# M632B.net
KiCad netlist of a schematic drawn in EAGLE
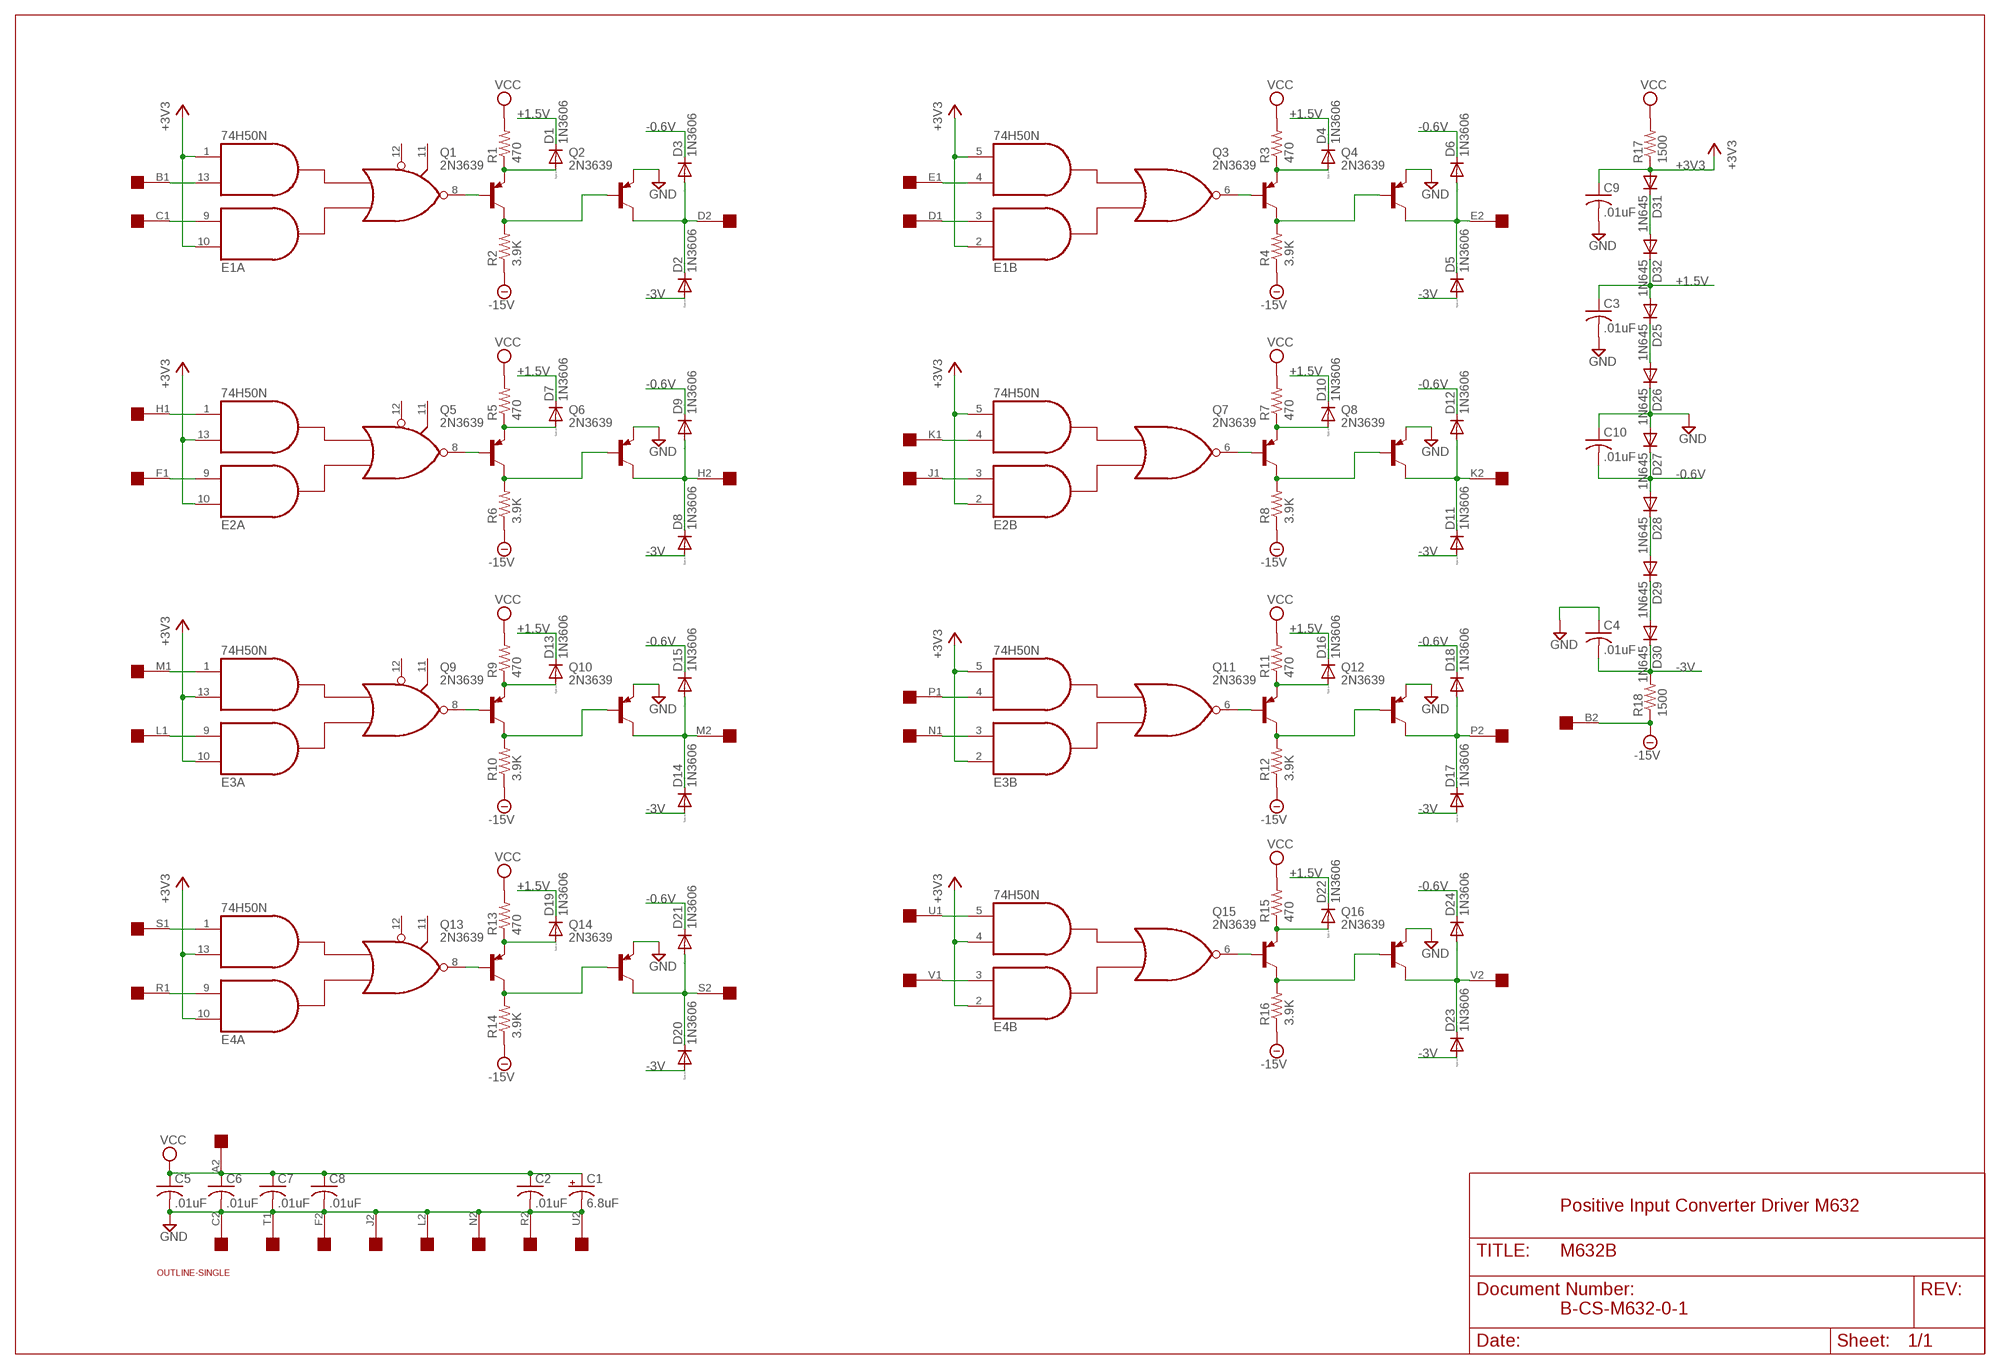
[diagram p0: schematic, sheet 1]

(export (version "E")
  (design (tool "Eeschema 10.0.6"))
  (components
    (comp (ref "C1")
      (value "6.8uF")
      (footprint "eagle-import:E12-8")
      (libsource (lib "eagle-import") (part "CPOL-USE20-8AXIAL"))
    )
    (comp (ref "C2")
      (value ".01uF")
      (footprint "eagle-import:C050-025X075")
      (libsource (lib "eagle-import") (part "C-US050-025X075"))
    )
    (comp (ref "C3")
      (value ".01uF")
      (footprint "eagle-import:C050-025X075")
      (libsource (lib "eagle-import") (part "C-US050-025X075"))
    )
    (comp (ref "C4")
      (value ".01uF")
      (footprint "eagle-import:C050-025X075")
      (libsource (lib "eagle-import") (part "C-US050-025X075"))
    )
    (comp (ref "C5")
      (value ".01uF")
      (footprint "eagle-import:C050-025X075")
      (libsource (lib "eagle-import") (part "C-US050-025X075"))
    )
    (comp (ref "C6")
      (value ".01uF")
      (footprint "eagle-import:C050-025X075")
      (libsource (lib "eagle-import") (part "C-US050-025X075"))
    )
    (comp (ref "C7")
      (value ".01uF")
      (footprint "eagle-import:C050-025X075")
      (libsource (lib "eagle-import") (part "C-US050-025X075"))
    )
    (comp (ref "C8")
      (value ".01uF")
      (footprint "eagle-import:C050-025X075")
      (libsource (lib "eagle-import") (part "C-US050-025X075"))
    )
    (comp (ref "C9")
      (value ".01uF")
      (footprint "eagle-import:C050-025X075")
      (libsource (lib "eagle-import") (part "C-US050-025X075"))
    )
    (comp (ref "C10")
      (value ".01uF")
      (footprint "eagle-import:C050-025X075")
      (libsource (lib "eagle-import") (part "C-US050-025X075"))
    )
    (comp (ref "D1")
      (value "1N3606")
      (footprint "eagle-import:DO35-10")
      (libsource (lib "eagle-import") (part "1N4148DO35-10"))
    )
    (comp (ref "D2")
      (value "1N3606")
      (footprint "eagle-import:DO35-10")
      (libsource (lib "eagle-import") (part "1N4148DO35-10"))
    )
    (comp (ref "D3")
      (value "1N3606")
      (footprint "eagle-import:DO35-10")
      (libsource (lib "eagle-import") (part "1N4148DO35-10"))
    )
    (comp (ref "D4")
      (value "1N3606")
      (footprint "eagle-import:DO35-10")
      (libsource (lib "eagle-import") (part "1N4148DO35-10"))
    )
    (comp (ref "D5")
      (value "1N3606")
      (footprint "eagle-import:DO35-10")
      (libsource (lib "eagle-import") (part "1N4148DO35-10"))
    )
    (comp (ref "D6")
      (value "1N3606")
      (footprint "eagle-import:DO35-10")
      (libsource (lib "eagle-import") (part "1N4148DO35-10"))
    )
    (comp (ref "D7")
      (value "1N3606")
      (footprint "eagle-import:DO35-10")
      (libsource (lib "eagle-import") (part "1N4148DO35-10"))
    )
    (comp (ref "D8")
      (value "1N3606")
      (footprint "eagle-import:DO35-10")
      (libsource (lib "eagle-import") (part "1N4148DO35-10"))
    )
    (comp (ref "D9")
      (value "1N3606")
      (footprint "eagle-import:DO35-10")
      (libsource (lib "eagle-import") (part "1N4148DO35-10"))
    )
    (comp (ref "D10")
      (value "1N3606")
      (footprint "eagle-import:DO35-10")
      (libsource (lib "eagle-import") (part "1N4148DO35-10"))
    )
    (comp (ref "D11")
      (value "1N3606")
      (footprint "eagle-import:DO35-10")
      (libsource (lib "eagle-import") (part "1N4148DO35-10"))
    )
    (comp (ref "D12")
      (value "1N3606")
      (footprint "eagle-import:DO35-10")
      (libsource (lib "eagle-import") (part "1N4148DO35-10"))
    )
    (comp (ref "D13")
      (value "1N3606")
      (footprint "eagle-import:DO35-10")
      (libsource (lib "eagle-import") (part "1N4148DO35-10"))
    )
    (comp (ref "D14")
      (value "1N3606")
      (footprint "eagle-import:DO35-10")
      (libsource (lib "eagle-import") (part "1N4148DO35-10"))
    )
    (comp (ref "D15")
      (value "1N3606")
      (footprint "eagle-import:DO35-10")
      (libsource (lib "eagle-import") (part "1N4148DO35-10"))
    )
    (comp (ref "D16")
      (value "1N3606")
      (footprint "eagle-import:DO35-10")
      (libsource (lib "eagle-import") (part "1N4148DO35-10"))
    )
    (comp (ref "D17")
      (value "1N3606")
      (footprint "eagle-import:DO35-10")
      (libsource (lib "eagle-import") (part "1N4148DO35-10"))
    )
    (comp (ref "D18")
      (value "1N3606")
      (footprint "eagle-import:DO35-10")
      (libsource (lib "eagle-import") (part "1N4148DO35-10"))
    )
    (comp (ref "D19")
      (value "1N3606")
      (footprint "eagle-import:DO35-10")
      (libsource (lib "eagle-import") (part "1N4148DO35-10"))
    )
    (comp (ref "D20")
      (value "1N3606")
      (footprint "eagle-import:DO35-10")
      (libsource (lib "eagle-import") (part "1N4148DO35-10"))
    )
    (comp (ref "D21")
      (value "1N3606")
      (footprint "eagle-import:DO35-10")
      (libsource (lib "eagle-import") (part "1N4148DO35-10"))
    )
    (comp (ref "D22")
      (value "1N3606")
      (footprint "eagle-import:DO35-10")
      (libsource (lib "eagle-import") (part "1N4148DO35-10"))
    )
    (comp (ref "D23")
      (value "1N3606")
      (footprint "eagle-import:DO35-10")
      (libsource (lib "eagle-import") (part "1N4148DO35-10"))
    )
    (comp (ref "D24")
      (value "1N3606")
      (footprint "eagle-import:DO35-10")
      (libsource (lib "eagle-import") (part "1N4148DO35-10"))
    )
    (comp (ref "D25")
      (value "1N645")
      (footprint "eagle-import:DO35-10")
      (libsource (lib "eagle-import") (part "1N4148DO35-10"))
    )
    (comp (ref "D26")
      (value "1N645")
      (footprint "eagle-import:DO35-10")
      (libsource (lib "eagle-import") (part "1N4148DO35-10"))
    )
    (comp (ref "D27")
      (value "1N645")
      (footprint "eagle-import:DO35-10")
      (libsource (lib "eagle-import") (part "1N4148DO35-10"))
    )
    (comp (ref "D28")
      (value "1N645")
      (footprint "eagle-import:DO35-10")
      (libsource (lib "eagle-import") (part "1N4148DO35-10"))
    )
    (comp (ref "D29")
      (value "1N645")
      (footprint "eagle-import:DO35-10")
      (libsource (lib "eagle-import") (part "1N4148DO35-10"))
    )
    (comp (ref "D30")
      (value "1N645")
      (footprint "eagle-import:DO35-10")
      (libsource (lib "eagle-import") (part "1N4148DO35-10"))
    )
    (comp (ref "D31")
      (value "1N645")
      (footprint "eagle-import:DO35-10")
      (libsource (lib "eagle-import") (part "1N4148DO35-10"))
    )
    (comp (ref "D32")
      (value "1N645")
      (footprint "eagle-import:DO35-10")
      (libsource (lib "eagle-import") (part "1N4148DO35-10"))
    )
    (comp (ref "E1")
      (value "74H50N")
      (footprint "eagle-import:DIL14")
      (libsource (lib "eagle-import") (part "7450N"))
    )
    (comp (ref "E2")
      (value "74H50N")
      (footprint "eagle-import:DIL14")
      (libsource (lib "eagle-import") (part "7450N"))
    )
    (comp (ref "E3")
      (value "74H50N")
      (footprint "eagle-import:DIL14")
      (libsource (lib "eagle-import") (part "7450N"))
    )
    (comp (ref "E4")
      (value "74H50N")
      (footprint "eagle-import:DIL14")
      (libsource (lib "eagle-import") (part "7450N"))
    )
    (comp (ref "Q1")
      (value "2N3639")
      (footprint "eagle-import:TO39")
      (libsource (lib "eagle-import") (part "2N2904"))
    )
    (comp (ref "Q2")
      (value "2N3639")
      (footprint "eagle-import:TO39")
      (libsource (lib "eagle-import") (part "2N2904"))
    )
    (comp (ref "Q3")
      (value "2N3639")
      (footprint "eagle-import:TO39")
      (libsource (lib "eagle-import") (part "2N2904"))
    )
    (comp (ref "Q4")
      (value "2N3639")
      (footprint "eagle-import:TO39")
      (libsource (lib "eagle-import") (part "2N2904"))
    )
    (comp (ref "Q5")
      (value "2N3639")
      (footprint "eagle-import:TO39")
      (libsource (lib "eagle-import") (part "2N2904"))
    )
    (comp (ref "Q6")
      (value "2N3639")
      (footprint "eagle-import:TO39")
      (libsource (lib "eagle-import") (part "2N2904"))
    )
    (comp (ref "Q7")
      (value "2N3639")
      (footprint "eagle-import:TO39")
      (libsource (lib "eagle-import") (part "2N2904"))
    )
    (comp (ref "Q8")
      (value "2N3639")
      (footprint "eagle-import:TO39")
      (libsource (lib "eagle-import") (part "2N2904"))
    )
    (comp (ref "Q9")
      (value "2N3639")
      (footprint "eagle-import:TO39")
      (libsource (lib "eagle-import") (part "2N2904"))
    )
    (comp (ref "Q10")
      (value "2N3639")
      (footprint "eagle-import:TO39")
      (libsource (lib "eagle-import") (part "2N2904"))
    )
    (comp (ref "Q11")
      (value "2N3639")
      (footprint "eagle-import:TO39")
      (libsource (lib "eagle-import") (part "2N2904"))
    )
    (comp (ref "Q12")
      (value "2N3639")
      (footprint "eagle-import:TO39")
      (libsource (lib "eagle-import") (part "2N2904"))
    )
    (comp (ref "Q13")
      (value "2N3639")
      (footprint "eagle-import:TO39")
      (libsource (lib "eagle-import") (part "2N2904"))
    )
    (comp (ref "Q14")
      (value "2N3639")
      (footprint "eagle-import:TO39")
      (libsource (lib "eagle-import") (part "2N2904"))
    )
    (comp (ref "Q15")
      (value "2N3639")
      (footprint "eagle-import:TO39")
      (libsource (lib "eagle-import") (part "2N2904"))
    )
    (comp (ref "Q16")
      (value "2N3639")
      (footprint "eagle-import:TO39")
      (libsource (lib "eagle-import") (part "2N2904"))
    )
    (comp (ref "R1")
      (value "470")
      (footprint "eagle-import:0207_10")
      (libsource (lib "eagle-import") (part "R-US_0207/10"))
    )
    (comp (ref "R2")
      (value "3.9K")
      (footprint "eagle-import:0207_10")
      (libsource (lib "eagle-import") (part "R-US_0207/10"))
    )
    (comp (ref "R3")
      (value "470")
      (footprint "eagle-import:0207_10")
      (libsource (lib "eagle-import") (part "R-US_0207/10"))
    )
    (comp (ref "R4")
      (value "3.9K")
      (footprint "eagle-import:0207_10")
      (libsource (lib "eagle-import") (part "R-US_0207/10"))
    )
    (comp (ref "R5")
      (value "470")
      (footprint "eagle-import:0207_10")
      (libsource (lib "eagle-import") (part "R-US_0207/10"))
    )
    (comp (ref "R6")
      (value "3.9K")
      (footprint "eagle-import:0207_10")
      (libsource (lib "eagle-import") (part "R-US_0207/10"))
    )
    (comp (ref "R7")
      (value "470")
      (footprint "eagle-import:0207_10")
      (libsource (lib "eagle-import") (part "R-US_0207/10"))
    )
    (comp (ref "R8")
      (value "3.9K")
      (footprint "eagle-import:0207_10")
      (libsource (lib "eagle-import") (part "R-US_0207/10"))
    )
    (comp (ref "R9")
      (value "470")
      (footprint "eagle-import:0207_10")
      (libsource (lib "eagle-import") (part "R-US_0207/10"))
    )
    (comp (ref "R10")
      (value "3.9K")
      (footprint "eagle-import:0207_10")
      (libsource (lib "eagle-import") (part "R-US_0207/10"))
    )
    (comp (ref "R11")
      (value "470")
      (footprint "eagle-import:0207_10")
      (libsource (lib "eagle-import") (part "R-US_0207/10"))
    )
    (comp (ref "R12")
      (value "3.9K")
      (footprint "eagle-import:0207_10")
      (libsource (lib "eagle-import") (part "R-US_0207/10"))
    )
    (comp (ref "R13")
      (value "470")
      (footprint "eagle-import:0207_10")
      (libsource (lib "eagle-import") (part "R-US_0207/10"))
    )
    (comp (ref "R14")
      (value "3.9K")
      (footprint "eagle-import:0207_10")
      (libsource (lib "eagle-import") (part "R-US_0207/10"))
    )
    (comp (ref "R15")
      (value "470")
      (footprint "eagle-import:0207_10")
      (libsource (lib "eagle-import") (part "R-US_0207/10"))
    )
    (comp (ref "R16")
      (value "3.9K")
      (footprint "eagle-import:0207_10")
      (libsource (lib "eagle-import") (part "R-US_0207/10"))
    )
    (comp (ref "R17")
      (value "1500")
      (footprint "eagle-import:0207_10")
      (libsource (lib "eagle-import") (part "R-US_0207/10"))
    )
    (comp (ref "R18")
      (value "1500")
      (footprint "eagle-import:0207_10")
      (libsource (lib "eagle-import") (part "R-US_0207/10"))
    )
    (comp (ref "U$1")
      (value "SINGLE")
      (footprint "eagle-import:EDGE-CON2")
      (libsource (lib "eagle-import") (part "SINGLE"))
    )
    (comp (ref "U$4")
      (value "OUTLINE-SINGLE")
      (footprint "eagle-import:SINGLE")
      (libsource (lib "eagle-import") (part "OUTLINE-SINGLE"))
    )
  )
  (nets
    (net (code "1") (name "+3V3") (class "Default")
      (node (ref "C9") (pin "1") (pinfunction "1_1") (pintype "passive"))
      (node (ref "D31") (pin "A") (pinfunction "A_A") (pintype "passive"))
      (node (ref "E1") (pin "1") (pinfunction "I4_1") (pintype "input"))
      (node (ref "E1") (pin "10") (pinfunction "I1_10") (pintype "input"))
      (node (ref "E1") (pin "2") (pinfunction "I1_2") (pintype "input"))
      (node (ref "E1") (pin "5") (pinfunction "I4_5") (pintype "input"))
      (node (ref "E2") (pin "10") (pinfunction "I1_10") (pintype "input"))
      (node (ref "E2") (pin "13") (pinfunction "I3_13") (pintype "input"))
      (node (ref "E2") (pin "2") (pinfunction "I1_2") (pintype "input"))
      (node (ref "E2") (pin "5") (pinfunction "I4_5") (pintype "input"))
      (node (ref "E3") (pin "10") (pinfunction "I1_10") (pintype "input"))
      (node (ref "E3") (pin "13") (pinfunction "I3_13") (pintype "input"))
      (node (ref "E3") (pin "2") (pinfunction "I1_2") (pintype "input"))
      (node (ref "E3") (pin "5") (pinfunction "I4_5") (pintype "input"))
      (node (ref "E4") (pin "10") (pinfunction "I1_10") (pintype "input"))
      (node (ref "E4") (pin "13") (pinfunction "I3_13") (pintype "input"))
      (node (ref "E4") (pin "2") (pinfunction "I1_2") (pintype "input"))
      (node (ref "E4") (pin "4") (pinfunction "I3_4") (pintype "input"))
      (node (ref "R17") (pin "1") (pinfunction "1_1") (pintype "passive"))
    )
    (net (code "2") (name "-15V") (class "Default")
      (node (ref "R10") (pin "1") (pinfunction "1_1") (pintype "passive"))
      (node (ref "R12") (pin "1") (pinfunction "1_1") (pintype "passive"))
      (node (ref "R14") (pin "1") (pinfunction "1_1") (pintype "passive"))
      (node (ref "R16") (pin "1") (pinfunction "1_1") (pintype "passive"))
      (node (ref "R18") (pin "1") (pinfunction "1_1") (pintype "passive"))
      (node (ref "R2") (pin "1") (pinfunction "1_1") (pintype "passive"))
      (node (ref "R4") (pin "1") (pinfunction "1_1") (pintype "passive"))
      (node (ref "R6") (pin "1") (pinfunction "1_1") (pintype "passive"))
      (node (ref "R8") (pin "1") (pinfunction "1_1") (pintype "passive"))
      (node (ref "U$1") (pin "B2") (pinfunction "1_B2") (pintype "bidirectional"))
    )
    (net (code "3") (name "/+1.5V") (class "Default")
      (node (ref "C3") (pin "1") (pinfunction "1_1") (pintype "passive"))
      (node (ref "D1") (pin "C") (pinfunction "C_C") (pintype "passive"))
      (node (ref "D10") (pin "C") (pinfunction "C_C") (pintype "passive"))
      (node (ref "D13") (pin "C") (pinfunction "C_C") (pintype "passive"))
      (node (ref "D16") (pin "C") (pinfunction "C_C") (pintype "passive"))
      (node (ref "D19") (pin "C") (pinfunction "C_C") (pintype "passive"))
      (node (ref "D22") (pin "C") (pinfunction "C_C") (pintype "passive"))
      (node (ref "D25") (pin "A") (pinfunction "A_A") (pintype "passive"))
      (node (ref "D32") (pin "C") (pinfunction "C_C") (pintype "passive"))
      (node (ref "D4") (pin "C") (pinfunction "C_C") (pintype "passive"))
      (node (ref "D7") (pin "C") (pinfunction "C_C") (pintype "passive"))
    )
    (net (code "4") (name "/-0.6V") (class "Default")
      (node (ref "C10") (pin "2") (pinfunction "2_2") (pintype "passive"))
      (node (ref "D12") (pin "C") (pinfunction "C_C") (pintype "passive"))
      (node (ref "D15") (pin "C") (pinfunction "C_C") (pintype "passive"))
      (node (ref "D18") (pin "C") (pinfunction "C_C") (pintype "passive"))
      (node (ref "D21") (pin "C") (pinfunction "C_C") (pintype "passive"))
      (node (ref "D24") (pin "C") (pinfunction "C_C") (pintype "passive"))
      (node (ref "D27") (pin "C") (pinfunction "C_C") (pintype "passive"))
      (node (ref "D28") (pin "A") (pinfunction "A_A") (pintype "passive"))
      (node (ref "D3") (pin "C") (pinfunction "C_C") (pintype "passive"))
      (node (ref "D6") (pin "C") (pinfunction "C_C") (pintype "passive"))
      (node (ref "D9") (pin "C") (pinfunction "C_C") (pintype "passive"))
    )
    (net (code "5") (name "/-3V") (class "Default")
      (node (ref "C4") (pin "2") (pinfunction "2_2") (pintype "passive"))
      (node (ref "D11") (pin "A") (pinfunction "A_A") (pintype "passive"))
      (node (ref "D14") (pin "A") (pinfunction "A_A") (pintype "passive"))
      (node (ref "D17") (pin "A") (pinfunction "A_A") (pintype "passive"))
      (node (ref "D2") (pin "A") (pinfunction "A_A") (pintype "passive"))
      (node (ref "D20") (pin "A") (pinfunction "A_A") (pintype "passive"))
      (node (ref "D23") (pin "A") (pinfunction "A_A") (pintype "passive"))
      (node (ref "D30") (pin "C") (pinfunction "C_C") (pintype "passive"))
      (node (ref "D5") (pin "A") (pinfunction "A_A") (pintype "passive"))
      (node (ref "D8") (pin "A") (pinfunction "A_A") (pintype "passive"))
      (node (ref "R18") (pin "2") (pinfunction "2_2") (pintype "passive"))
    )
    (net (code "6") (name "GND") (class "Default")
      (node (ref "C1") (pin "-") (pinfunction "-_-") (pintype "passive"))
      (node (ref "C10") (pin "1") (pinfunction "1_1") (pintype "passive"))
      (node (ref "C2") (pin "2") (pinfunction "2_2") (pintype "passive"))
      (node (ref "C3") (pin "2") (pinfunction "2_2") (pintype "passive"))
      (node (ref "C4") (pin "1") (pinfunction "1_1") (pintype "passive"))
      (node (ref "C5") (pin "2") (pinfunction "2_2") (pintype "passive"))
      (node (ref "C6") (pin "2") (pinfunction "2_2") (pintype "passive"))
      (node (ref "C7") (pin "2") (pinfunction "2_2") (pintype "passive"))
      (node (ref "C8") (pin "2") (pinfunction "2_2") (pintype "passive"))
      (node (ref "C9") (pin "2") (pinfunction "2_2") (pintype "passive"))
      (node (ref "D26") (pin "C") (pinfunction "C_C") (pintype "passive"))
      (node (ref "D27") (pin "A") (pinfunction "A_A") (pintype "passive"))
      (node (ref "Q10") (pin "1") (pinfunction "E_1") (pintype "passive"))
      (node (ref "Q12") (pin "1") (pinfunction "E_1") (pintype "passive"))
      (node (ref "Q14") (pin "1") (pinfunction "E_1") (pintype "passive"))
      (node (ref "Q16") (pin "1") (pinfunction "E_1") (pintype "passive"))
      (node (ref "Q2") (pin "1") (pinfunction "E_1") (pintype "passive"))
      (node (ref "Q4") (pin "1") (pinfunction "E_1") (pintype "passive"))
      (node (ref "Q6") (pin "1") (pinfunction "E_1") (pintype "passive"))
      (node (ref "Q8") (pin "1") (pinfunction "E_1") (pintype "passive"))
      (node (ref "U$1") (pin "C2") (pinfunction "1_C2") (pintype "bidirectional"))
      (node (ref "U$1") (pin "F2") (pinfunction "1_F2") (pintype "bidirectional"))
      (node (ref "U$1") (pin "J2") (pinfunction "1_J2") (pintype "bidirectional"))
      (node (ref "U$1") (pin "L2") (pinfunction "1_L2") (pintype "bidirectional"))
      (node (ref "U$1") (pin "N2") (pinfunction "1_N2") (pintype "bidirectional"))
      (node (ref "U$1") (pin "R2") (pinfunction "1_R2") (pintype "bidirectional"))
      (node (ref "U$1") (pin "T1") (pinfunction "1_T1") (pintype "bidirectional"))
      (node (ref "U$1") (pin "U2") (pinfunction "1_U2") (pintype "bidirectional"))
    )
    (net (code "7") (name "Net-(D25-PadC)") (class "Default")
      (node (ref "D25") (pin "C") (pinfunction "C_C") (pintype "passive"))
      (node (ref "D26") (pin "A") (pinfunction "A_A") (pintype "passive"))
    )
    (net (code "8") (name "Net-(D28-PadC)") (class "Default")
      (node (ref "D28") (pin "C") (pinfunction "C_C") (pintype "passive"))
      (node (ref "D29") (pin "A") (pinfunction "A_A") (pintype "passive"))
    )
    (net (code "9") (name "Net-(D29-PadC)") (class "Default")
      (node (ref "D29") (pin "C") (pinfunction "C_C") (pintype "passive"))
      (node (ref "D30") (pin "A") (pinfunction "A_A") (pintype "passive"))
    )
    (net (code "10") (name "Net-(D31-PadC)") (class "Default")
      (node (ref "D31") (pin "C") (pinfunction "C_C") (pintype "passive"))
      (node (ref "D32") (pin "A") (pinfunction "A_A") (pintype "passive"))
    )
    (net (code "11") (name "Net-(E1A-I2)") (class "Default")
      (node (ref "E1") (pin "9") (pinfunction "I2_9") (pintype "input"))
      (node (ref "U$1") (pin "C1") (pinfunction "1_C1") (pintype "bidirectional"))
    )
    (net (code "12") (name "Net-(E1A-I3)") (class "Default")
      (node (ref "E1") (pin "13") (pinfunction "I3_13") (pintype "input"))
      (node (ref "U$1") (pin "B1") (pinfunction "1_B1") (pintype "bidirectional"))
    )
    (net (code "13") (name "Net-(E1A-O)") (class "Default")
      (node (ref "E1") (pin "8") (pinfunction "O_8") (pintype "output"))
      (node (ref "Q1") (pin "2") (pinfunction "B_2") (pintype "passive"))
    )
    (net (code "14") (name "Net-(E1B-I2)") (class "Default")
      (node (ref "E1") (pin "3") (pinfunction "I2_3") (pintype "input"))
      (node (ref "U$1") (pin "D1") (pinfunction "1_D1") (pintype "bidirectional"))
    )
    (net (code "15") (name "Net-(E1B-I3)") (class "Default")
      (node (ref "E1") (pin "4") (pinfunction "I3_4") (pintype "input"))
      (node (ref "U$1") (pin "E1") (pinfunction "1_E1") (pintype "bidirectional"))
    )
    (net (code "16") (name "Net-(E1B-O)") (class "Default")
      (node (ref "E1") (pin "6") (pinfunction "O_6") (pintype "output"))
      (node (ref "Q3") (pin "2") (pinfunction "B_2") (pintype "passive"))
    )
    (net (code "17") (name "Net-(E2A-I2)") (class "Default")
      (node (ref "E2") (pin "9") (pinfunction "I2_9") (pintype "input"))
      (node (ref "U$1") (pin "F1") (pinfunction "1_F1") (pintype "bidirectional"))
    )
    (net (code "18") (name "Net-(E2A-I4)") (class "Default")
      (node (ref "E2") (pin "1") (pinfunction "I4_1") (pintype "input"))
      (node (ref "U$1") (pin "H1") (pinfunction "1_H1") (pintype "bidirectional"))
    )
    (net (code "19") (name "Net-(E2A-O)") (class "Default")
      (node (ref "E2") (pin "8") (pinfunction "O_8") (pintype "output"))
      (node (ref "Q5") (pin "2") (pinfunction "B_2") (pintype "passive"))
    )
    (net (code "20") (name "Net-(E2B-I2)") (class "Default")
      (node (ref "E2") (pin "3") (pinfunction "I2_3") (pintype "input"))
      (node (ref "U$1") (pin "J1") (pinfunction "1_J1") (pintype "bidirectional"))
    )
    (net (code "21") (name "Net-(E2B-I3)") (class "Default")
      (node (ref "E2") (pin "4") (pinfunction "I3_4") (pintype "input"))
      (node (ref "U$1") (pin "K1") (pinfunction "1_K1") (pintype "bidirectional"))
    )
    (net (code "22") (name "Net-(E2B-O)") (class "Default")
      (node (ref "E2") (pin "6") (pinfunction "O_6") (pintype "output"))
      (node (ref "Q7") (pin "2") (pinfunction "B_2") (pintype "passive"))
    )
    (net (code "23") (name "Net-(E3A-I2)") (class "Default")
      (node (ref "E3") (pin "9") (pinfunction "I2_9") (pintype "input"))
      (node (ref "U$1") (pin "L1") (pinfunction "1_L1") (pintype "bidirectional"))
    )
    (net (code "24") (name "Net-(E3A-I4)") (class "Default")
      (node (ref "E3") (pin "1") (pinfunction "I4_1") (pintype "input"))
      (node (ref "U$1") (pin "M1") (pinfunction "1_M1") (pintype "bidirectional"))
    )
    (net (code "25") (name "Net-(E3A-O)") (class "Default")
      (node (ref "E3") (pin "8") (pinfunction "O_8") (pintype "output"))
      (node (ref "Q9") (pin "2") (pinfunction "B_2") (pintype "passive"))
    )
    (net (code "26") (name "Net-(E3B-I2)") (class "Default")
      (node (ref "E3") (pin "3") (pinfunction "I2_3") (pintype "input"))
      (node (ref "U$1") (pin "N1") (pinfunction "1_N1") (pintype "bidirectional"))
    )
    (net (code "27") (name "Net-(E3B-I3)") (class "Default")
      (node (ref "E3") (pin "4") (pinfunction "I3_4") (pintype "input"))
      (node (ref "U$1") (pin "P1") (pinfunction "1_P1") (pintype "bidirectional"))
    )
    (net (code "28") (name "Net-(E3B-O)") (class "Default")
      (node (ref "E3") (pin "6") (pinfunction "O_6") (pintype "output"))
      (node (ref "Q11") (pin "2") (pinfunction "B_2") (pintype "passive"))
    )
    (net (code "29") (name "Net-(E4A-I2)") (class "Default")
      (node (ref "E4") (pin "9") (pinfunction "I2_9") (pintype "input"))
      (node (ref "U$1") (pin "R1") (pinfunction "1_R1") (pintype "bidirectional"))
    )
    (net (code "30") (name "Net-(E4A-I4)") (class "Default")
      (node (ref "E4") (pin "1") (pinfunction "I4_1") (pintype "input"))
      (node (ref "U$1") (pin "S1") (pinfunction "1_S1") (pintype "bidirectional"))
    )
    (net (code "31") (name "Net-(E4A-O)") (class "Default")
      (node (ref "E4") (pin "8") (pinfunction "O_8") (pintype "output"))
      (node (ref "Q13") (pin "2") (pinfunction "B_2") (pintype "passive"))
    )
    (net (code "32") (name "Net-(E4B-I2)") (class "Default")
      (node (ref "E4") (pin "3") (pinfunction "I2_3") (pintype "input"))
      (node (ref "U$1") (pin "V1") (pinfunction "1_V1") (pintype "bidirectional"))
    )
    (net (code "33") (name "Net-(E4B-I4)") (class "Default")
      (node (ref "E4") (pin "5") (pinfunction "I4_5") (pintype "input"))
      (node (ref "U$1") (pin "U1") (pinfunction "1_U1") (pintype "bidirectional"))
    )
    (net (code "34") (name "Net-(E4B-O)") (class "Default")
      (node (ref "E4") (pin "6") (pinfunction "O_6") (pintype "output"))
      (node (ref "Q15") (pin "2") (pinfunction "B_2") (pintype "passive"))
    )
    (net (code "35") (name "Net-(Q1-C)") (class "Default")
      (node (ref "Q1") (pin "3") (pinfunction "C_3") (pintype "passive"))
      (node (ref "Q2") (pin "2") (pinfunction "B_2") (pintype "passive"))
      (node (ref "R2") (pin "2") (pinfunction "2_2") (pintype "passive"))
    )
    (net (code "36") (name "Net-(Q1-E)") (class "Default")
      (node (ref "D1") (pin "A") (pinfunction "A_A") (pintype "passive"))
      (node (ref "Q1") (pin "1") (pinfunction "E_1") (pintype "passive"))
      (node (ref "R1") (pin "1") (pinfunction "1_1") (pintype "passive"))
    )
    (net (code "37") (name "Net-(Q2-C)") (class "Default")
      (node (ref "D2") (pin "C") (pinfunction "C_C") (pintype "passive"))
      (node (ref "D3") (pin "A") (pinfunction "A_A") (pintype "passive"))
      (node (ref "Q2") (pin "3") (pinfunction "C_3") (pintype "passive"))
      (node (ref "U$1") (pin "D2") (pinfunction "1_D2") (pintype "bidirectional"))
    )
    (net (code "38") (name "Net-(Q3-C)") (class "Default")
      (node (ref "Q3") (pin "3") (pinfunction "C_3") (pintype "passive"))
      (node (ref "Q4") (pin "2") (pinfunction "B_2") (pintype "passive"))
      (node (ref "R4") (pin "2") (pinfunction "2_2") (pintype "passive"))
    )
    (net (code "39") (name "Net-(Q3-E)") (class "Default")
      (node (ref "D4") (pin "A") (pinfunction "A_A") (pintype "passive"))
      (node (ref "Q3") (pin "1") (pinfunction "E_1") (pintype "passive"))
      (node (ref "R3") (pin "1") (pinfunction "1_1") (pintype "passive"))
    )
    (net (code "40") (name "Net-(Q4-C)") (class "Default")
      (node (ref "D5") (pin "C") (pinfunction "C_C") (pintype "passive"))
      (node (ref "D6") (pin "A") (pinfunction "A_A") (pintype "passive"))
      (node (ref "Q4") (pin "3") (pinfunction "C_3") (pintype "passive"))
      (node (ref "U$1") (pin "E2") (pinfunction "1_E2") (pintype "bidirectional"))
    )
    (net (code "41") (name "Net-(Q5-C)") (class "Default")
      (node (ref "Q5") (pin "3") (pinfunction "C_3") (pintype "passive"))
      (node (ref "Q6") (pin "2") (pinfunction "B_2") (pintype "passive"))
      (node (ref "R6") (pin "2") (pinfunction "2_2") (pintype "passive"))
    )
    (net (code "42") (name "Net-(Q5-E)") (class "Default")
      (node (ref "D7") (pin "A") (pinfunction "A_A") (pintype "passive"))
      (node (ref "Q5") (pin "1") (pinfunction "E_1") (pintype "passive"))
      (node (ref "R5") (pin "1") (pinfunction "1_1") (pintype "passive"))
    )
    (net (code "43") (name "Net-(Q6-C)") (class "Default")
      (node (ref "D8") (pin "C") (pinfunction "C_C") (pintype "passive"))
      (node (ref "D9") (pin "A") (pinfunction "A_A") (pintype "passive"))
      (node (ref "Q6") (pin "3") (pinfunction "C_3") (pintype "passive"))
      (node (ref "U$1") (pin "H2") (pinfunction "1_H2") (pintype "bidirectional"))
    )
    (net (code "44") (name "Net-(Q7-C)") (class "Default")
      (node (ref "Q7") (pin "3") (pinfunction "C_3") (pintype "passive"))
      (node (ref "Q8") (pin "2") (pinfunction "B_2") (pintype "passive"))
      (node (ref "R8") (pin "2") (pinfunction "2_2") (pintype "passive"))
    )
    (net (code "45") (name "Net-(Q7-E)") (class "Default")
      (node (ref "D10") (pin "A") (pinfunction "A_A") (pintype "passive"))
      (node (ref "Q7") (pin "1") (pinfunction "E_1") (pintype "passive"))
      (node (ref "R7") (pin "1") (pinfunction "1_1") (pintype "passive"))
    )
    (net (code "46") (name "Net-(Q8-C)") (class "Default")
      (node (ref "D11") (pin "C") (pinfunction "C_C") (pintype "passive"))
      (node (ref "D12") (pin "A") (pinfunction "A_A") (pintype "passive"))
      (node (ref "Q8") (pin "3") (pinfunction "C_3") (pintype "passive"))
      (node (ref "U$1") (pin "K2") (pinfunction "1_K2") (pintype "bidirectional"))
    )
    (net (code "47") (name "Net-(Q9-E)") (class "Default")
      (node (ref "D13") (pin "A") (pinfunction "A_A") (pintype "passive"))
      (node (ref "Q9") (pin "1") (pinfunction "E_1") (pintype "passive"))
      (node (ref "R9") (pin "1") (pinfunction "1_1") (pintype "passive"))
    )
    (net (code "48") (name "Net-(Q10-B)") (class "Default")
      (node (ref "Q10") (pin "2") (pinfunction "B_2") (pintype "passive"))
      (node (ref "Q9") (pin "3") (pinfunction "C_3") (pintype "passive"))
      (node (ref "R10") (pin "2") (pinfunction "2_2") (pintype "passive"))
    )
    (net (code "49") (name "Net-(Q10-C)") (class "Default")
      (node (ref "D14") (pin "C") (pinfunction "C_C") (pintype "passive"))
      (node (ref "D15") (pin "A") (pinfunction "A_A") (pintype "passive"))
      (node (ref "Q10") (pin "3") (pinfunction "C_3") (pintype "passive"))
      (node (ref "U$1") (pin "M2") (pinfunction "1_M2") (pintype "bidirectional"))
    )
    (net (code "50") (name "Net-(Q11-C)") (class "Default")
      (node (ref "Q11") (pin "3") (pinfunction "C_3") (pintype "passive"))
      (node (ref "Q12") (pin "2") (pinfunction "B_2") (pintype "passive"))
      (node (ref "R12") (pin "2") (pinfunction "2_2") (pintype "passive"))
    )
    (net (code "51") (name "Net-(Q11-E)") (class "Default")
      (node (ref "D16") (pin "A") (pinfunction "A_A") (pintype "passive"))
      (node (ref "Q11") (pin "1") (pinfunction "E_1") (pintype "passive"))
      (node (ref "R11") (pin "1") (pinfunction "1_1") (pintype "passive"))
    )
    (net (code "52") (name "Net-(Q12-C)") (class "Default")
      (node (ref "D17") (pin "C") (pinfunction "C_C") (pintype "passive"))
      (node (ref "D18") (pin "A") (pinfunction "A_A") (pintype "passive"))
      (node (ref "Q12") (pin "3") (pinfunction "C_3") (pintype "passive"))
      (node (ref "U$1") (pin "P2") (pinfunction "1_P2") (pintype "bidirectional"))
    )
    (net (code "53") (name "Net-(Q13-C)") (class "Default")
      (node (ref "Q13") (pin "3") (pinfunction "C_3") (pintype "passive"))
      (node (ref "Q14") (pin "2") (pinfunction "B_2") (pintype "passive"))
      (node (ref "R14") (pin "2") (pinfunction "2_2") (pintype "passive"))
    )
    (net (code "54") (name "Net-(Q13-E)") (class "Default")
      (node (ref "D19") (pin "A") (pinfunction "A_A") (pintype "passive"))
      (node (ref "Q13") (pin "1") (pinfunction "E_1") (pintype "passive"))
      (node (ref "R13") (pin "1") (pinfunction "1_1") (pintype "passive"))
    )
    (net (code "55") (name "Net-(Q14-C)") (class "Default")
      (node (ref "D20") (pin "C") (pinfunction "C_C") (pintype "passive"))
      (node (ref "D21") (pin "A") (pinfunction "A_A") (pintype "passive"))
      (node (ref "Q14") (pin "3") (pinfunction "C_3") (pintype "passive"))
      (node (ref "U$1") (pin "S2") (pinfunction "1_S2") (pintype "bidirectional"))
    )
    (net (code "56") (name "Net-(Q15-C)") (class "Default")
      (node (ref "Q15") (pin "3") (pinfunction "C_3") (pintype "passive"))
      (node (ref "Q16") (pin "2") (pinfunction "B_2") (pintype "passive"))
      (node (ref "R16") (pin "2") (pinfunction "2_2") (pintype "passive"))
    )
    (net (code "57") (name "Net-(Q15-E)") (class "Default")
      (node (ref "D22") (pin "A") (pinfunction "A_A") (pintype "passive"))
      (node (ref "Q15") (pin "1") (pinfunction "E_1") (pintype "passive"))
      (node (ref "R15") (pin "1") (pinfunction "1_1") (pintype "passive"))
    )
    (net (code "58") (name "Net-(Q16-C)") (class "Default")
      (node (ref "D23") (pin "C") (pinfunction "C_C") (pintype "passive"))
      (node (ref "D24") (pin "A") (pinfunction "A_A") (pintype "passive"))
      (node (ref "Q16") (pin "3") (pinfunction "C_3") (pintype "passive"))
      (node (ref "U$1") (pin "V2") (pinfunction "1_V2") (pintype "bidirectional"))
    )
    (net (code "59") (name "VCC") (class "Default")
      (node (ref "C1") (pin "+") (pinfunction "+_+") (pintype "passive"))
      (node (ref "C2") (pin "1") (pinfunction "1_1") (pintype "passive"))
      (node (ref "C5") (pin "1") (pinfunction "1_1") (pintype "passive"))
      (node (ref "C6") (pin "1") (pinfunction "1_1") (pintype "passive"))
      (node (ref "C7") (pin "1") (pinfunction "1_1") (pintype "passive"))
      (node (ref "C8") (pin "1") (pinfunction "1_1") (pintype "passive"))
      (node (ref "R1") (pin "2") (pinfunction "2_2") (pintype "passive"))
      (node (ref "R11") (pin "2") (pinfunction "2_2") (pintype "passive"))
      (node (ref "R13") (pin "2") (pinfunction "2_2") (pintype "passive"))
      (node (ref "R15") (pin "2") (pinfunction "2_2") (pintype "passive"))
      (node (ref "R17") (pin "2") (pinfunction "2_2") (pintype "passive"))
      (node (ref "R3") (pin "2") (pinfunction "2_2") (pintype "passive"))
      (node (ref "R5") (pin "2") (pinfunction "2_2") (pintype "passive"))
      (node (ref "R7") (pin "2") (pinfunction "2_2") (pintype "passive"))
      (node (ref "R9") (pin "2") (pinfunction "2_2") (pintype "passive"))
      (node (ref "U$1") (pin "A2") (pinfunction "1_A2") (pintype "bidirectional"))
    )
    (net (code "60") (name "unconnected-(E1A-I5-Pad12)") (class "Default")
      (node (ref "E1") (pin "12") (pinfunction "I5_12") (pintype "passive"))
    )
    (net (code "61") (name "unconnected-(E1A-I6-Pad11)") (class "Default")
      (node (ref "E1") (pin "11") (pinfunction "I6_11") (pintype "passive"))
    )
    (net (code "62") (name "unconnected-(E2A-I5-Pad12)") (class "Default")
      (node (ref "E2") (pin "12") (pinfunction "I5_12") (pintype "passive"))
    )
    (net (code "63") (name "unconnected-(E2A-I6-Pad11)") (class "Default")
      (node (ref "E2") (pin "11") (pinfunction "I6_11") (pintype "passive"))
    )
    (net (code "64") (name "unconnected-(E3A-I5-Pad12)") (class "Default")
      (node (ref "E3") (pin "12") (pinfunction "I5_12") (pintype "passive"))
    )
    (net (code "65") (name "unconnected-(E3A-I6-Pad11)") (class "Default")
      (node (ref "E3") (pin "11") (pinfunction "I6_11") (pintype "passive"))
    )
    (net (code "66") (name "unconnected-(E4A-I5-Pad12)") (class "Default")
      (node (ref "E4") (pin "12") (pinfunction "I5_12") (pintype "passive"))
    )
    (net (code "67") (name "unconnected-(E4A-I6-Pad11)") (class "Default")
      (node (ref "E4") (pin "11") (pinfunction "I6_11") (pintype "passive"))
    )
  )
)
